# efi-shield-rev01.net
KiCad netlist of a schematic drawn in EAGLE
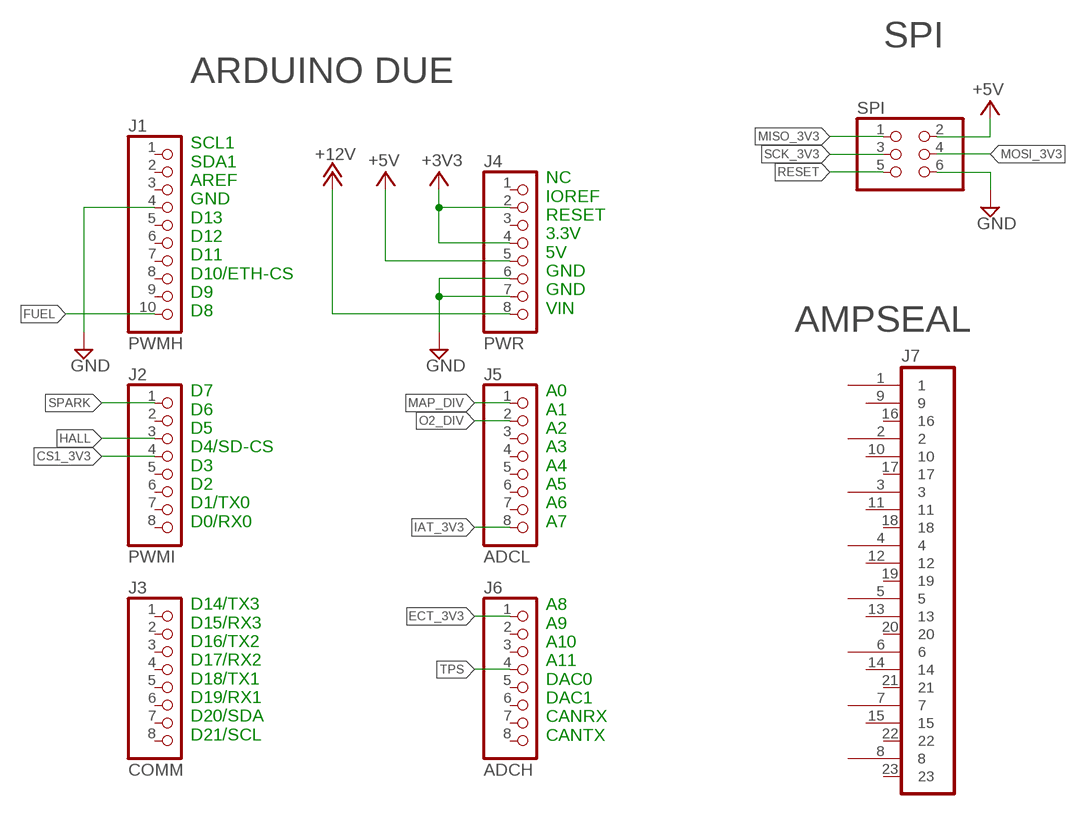
[diagram p0: schematic, sheet 1]

(export (version "E")
  (design (tool "Eeschema 10.0.6"))
  (components
    (comp (ref "J1")
      (value "PWMH")
      (footprint "eagle-import:1X10")
      (fields (field (name "MANUFACTURER") "Joe Knows Electronics"))
      (libsource (lib "eagle-import") (part "PINHD-1X10"))
    )
    (comp (ref "J2")
      (value "PWMI")
      (footprint "eagle-import:1X08")
      (fields (field (name "MANUFACTURER") "Joe Knows Electronics"))
      (libsource (lib "eagle-import") (part "PINHD-1X8"))
    )
    (comp (ref "J3")
      (value "COMM")
      (footprint "eagle-import:1X08")
      (fields (field (name "MANUFACTURER") "Joe Knows Electronics"))
      (libsource (lib "eagle-import") (part "PINHD-1X8"))
    )
    (comp (ref "J4")
      (value "PWR")
      (footprint "eagle-import:1X08")
      (fields (field (name "MANUFACTURER") "Joe Knows Electronics"))
      (libsource (lib "eagle-import") (part "PINHD-1X8"))
    )
    (comp (ref "J5")
      (value "ADCL")
      (footprint "eagle-import:1X08")
      (fields (field (name "MANUFACTURER") "Joe Knows Electronics"))
      (libsource (lib "eagle-import") (part "PINHD-1X8"))
    )
    (comp (ref "J6")
      (value "ADCH")
      (footprint "eagle-import:1X08")
      (fields (field (name "MANUFACTURER") "Joe Knows Electronics"))
      (libsource (lib "eagle-import") (part "PINHD-1X8"))
    )
    (comp (ref "J7")
      (value "AMPSEAL-23POS-HEADER")
      (footprint "eagle-import:AMPSEAL-HEADER-23POS-RA")
      (fields (field (name "MANUFACTURER") "TE Connectivity"))
      (libsource (lib "eagle-import") (part "AMPSEAL-23POS-HEADER"))
    )
    (comp (ref "SPI")
      (value "PINHD-2X3")
      (footprint "eagle-import:2X03")
      (libsource (lib "eagle-import") (part "PINHD-2X3"))
    )
  )
  (nets
    (net (code "1") (name "+3V3") (class "Default")
      (node (ref "J4") (pin "2") (pinfunction "2_2") (pintype "passive"))
      (node (ref "J4") (pin "4") (pinfunction "4_4") (pintype "passive"))
    )
    (net (code "2") (name "+5V") (class "Default")
      (node (ref "J4") (pin "5") (pinfunction "5_5") (pintype "passive"))
      (node (ref "SPI") (pin "2") (pinfunction "2_2") (pintype "passive"))
    )
    (net (code "3") (name "+12V") (class "Default")
      (node (ref "J4") (pin "8") (pinfunction "8_8") (pintype "passive"))
    )
    (net (code "4") (name "CS1_3V3") (class "Default")
      (node (ref "J2") (pin "4") (pinfunction "4_4") (pintype "passive"))
    )
    (net (code "5") (name "ECT_3V3") (class "Default")
      (node (ref "J6") (pin "1") (pinfunction "1_1") (pintype "passive"))
    )
    (net (code "6") (name "FUEL") (class "Default")
      (node (ref "J1") (pin "10") (pinfunction "10_10") (pintype "passive"))
    )
    (net (code "7") (name "GND") (class "Default")
      (node (ref "J1") (pin "4") (pinfunction "4_4") (pintype "passive"))
      (node (ref "J4") (pin "6") (pinfunction "6_6") (pintype "passive"))
      (node (ref "J4") (pin "7") (pinfunction "7_7") (pintype "passive"))
      (node (ref "SPI") (pin "6") (pinfunction "6_6") (pintype "passive"))
    )
    (net (code "8") (name "HALL") (class "Default")
      (node (ref "J2") (pin "3") (pinfunction "3_3") (pintype "passive"))
    )
    (net (code "9") (name "IAT_3V3") (class "Default")
      (node (ref "J5") (pin "8") (pinfunction "8_8") (pintype "passive"))
    )
    (net (code "10") (name "MAP_DIV") (class "Default")
      (node (ref "J5") (pin "1") (pinfunction "1_1") (pintype "passive"))
    )
    (net (code "11") (name "MISO_3V3") (class "Default")
      (node (ref "SPI") (pin "1") (pinfunction "1_1") (pintype "passive"))
    )
    (net (code "12") (name "MOSI_3V3") (class "Default")
      (node (ref "SPI") (pin "4") (pinfunction "4_4") (pintype "passive"))
    )
    (net (code "13") (name "O2_DIV") (class "Default")
      (node (ref "J5") (pin "2") (pinfunction "2_2") (pintype "passive"))
    )
    (net (code "14") (name "RESET") (class "Default")
      (node (ref "SPI") (pin "5") (pinfunction "5_5") (pintype "passive"))
    )
    (net (code "15") (name "SCK_3V3") (class "Default")
      (node (ref "SPI") (pin "3") (pinfunction "3_3") (pintype "passive"))
    )
    (net (code "16") (name "SPARK") (class "Default")
      (node (ref "J2") (pin "1") (pinfunction "1_1") (pintype "passive"))
    )
    (net (code "17") (name "TPS") (class "Default")
      (node (ref "J6") (pin "4") (pinfunction "4_4") (pintype "passive"))
    )
    (net (code "18") (name "unconnected-(J1-Pad1)") (class "Default")
      (node (ref "J1") (pin "1") (pinfunction "1_1") (pintype "passive"))
    )
    (net (code "19") (name "unconnected-(J1-Pad2)") (class "Default")
      (node (ref "J1") (pin "2") (pinfunction "2_2") (pintype "passive"))
    )
    (net (code "20") (name "unconnected-(J1-Pad3)") (class "Default")
      (node (ref "J1") (pin "3") (pinfunction "3_3") (pintype "passive"))
    )
    (net (code "21") (name "unconnected-(J1-Pad5)") (class "Default")
      (node (ref "J1") (pin "5") (pinfunction "5_5") (pintype "passive"))
    )
    (net (code "22") (name "unconnected-(J1-Pad6)") (class "Default")
      (node (ref "J1") (pin "6") (pinfunction "6_6") (pintype "passive"))
    )
    (net (code "23") (name "unconnected-(J1-Pad7)") (class "Default")
      (node (ref "J1") (pin "7") (pinfunction "7_7") (pintype "passive"))
    )
    (net (code "24") (name "unconnected-(J1-Pad8)") (class "Default")
      (node (ref "J1") (pin "8") (pinfunction "8_8") (pintype "passive"))
    )
    (net (code "25") (name "unconnected-(J1-Pad9)") (class "Default")
      (node (ref "J1") (pin "9") (pinfunction "9_9") (pintype "passive"))
    )
    (net (code "26") (name "unconnected-(J2-Pad2)") (class "Default")
      (node (ref "J2") (pin "2") (pinfunction "2_2") (pintype "passive"))
    )
    (net (code "27") (name "unconnected-(J2-Pad5)") (class "Default")
      (node (ref "J2") (pin "5") (pinfunction "5_5") (pintype "passive"))
    )
    (net (code "28") (name "unconnected-(J2-Pad6)") (class "Default")
      (node (ref "J2") (pin "6") (pinfunction "6_6") (pintype "passive"))
    )
    (net (code "29") (name "unconnected-(J2-Pad7)") (class "Default")
      (node (ref "J2") (pin "7") (pinfunction "7_7") (pintype "passive"))
    )
    (net (code "30") (name "unconnected-(J2-Pad8)") (class "Default")
      (node (ref "J2") (pin "8") (pinfunction "8_8") (pintype "passive"))
    )
    (net (code "31") (name "unconnected-(J3-Pad1)") (class "Default")
      (node (ref "J3") (pin "1") (pinfunction "1_1") (pintype "passive"))
    )
    (net (code "32") (name "unconnected-(J3-Pad2)") (class "Default")
      (node (ref "J3") (pin "2") (pinfunction "2_2") (pintype "passive"))
    )
    (net (code "33") (name "unconnected-(J3-Pad3)") (class "Default")
      (node (ref "J3") (pin "3") (pinfunction "3_3") (pintype "passive"))
    )
    (net (code "34") (name "unconnected-(J3-Pad4)") (class "Default")
      (node (ref "J3") (pin "4") (pinfunction "4_4") (pintype "passive"))
    )
    (net (code "35") (name "unconnected-(J3-Pad5)") (class "Default")
      (node (ref "J3") (pin "5") (pinfunction "5_5") (pintype "passive"))
    )
    (net (code "36") (name "unconnected-(J3-Pad6)") (class "Default")
      (node (ref "J3") (pin "6") (pinfunction "6_6") (pintype "passive"))
    )
    (net (code "37") (name "unconnected-(J3-Pad7)") (class "Default")
      (node (ref "J3") (pin "7") (pinfunction "7_7") (pintype "passive"))
    )
    (net (code "38") (name "unconnected-(J3-Pad8)") (class "Default")
      (node (ref "J3") (pin "8") (pinfunction "8_8") (pintype "passive"))
    )
    (net (code "39") (name "unconnected-(J4-Pad1)") (class "Default")
      (node (ref "J4") (pin "1") (pinfunction "1_1") (pintype "passive"))
    )
    (net (code "40") (name "unconnected-(J4-Pad3)") (class "Default")
      (node (ref "J4") (pin "3") (pinfunction "3_3") (pintype "passive"))
    )
    (net (code "41") (name "unconnected-(J5-Pad3)") (class "Default")
      (node (ref "J5") (pin "3") (pinfunction "3_3") (pintype "passive"))
    )
    (net (code "42") (name "unconnected-(J5-Pad4)") (class "Default")
      (node (ref "J5") (pin "4") (pinfunction "4_4") (pintype "passive"))
    )
    (net (code "43") (name "unconnected-(J5-Pad5)") (class "Default")
      (node (ref "J5") (pin "5") (pinfunction "5_5") (pintype "passive"))
    )
    (net (code "44") (name "unconnected-(J5-Pad6)") (class "Default")
      (node (ref "J5") (pin "6") (pinfunction "6_6") (pintype "passive"))
    )
    (net (code "45") (name "unconnected-(J5-Pad7)") (class "Default")
      (node (ref "J5") (pin "7") (pinfunction "7_7") (pintype "passive"))
    )
    (net (code "46") (name "unconnected-(J6-Pad2)") (class "Default")
      (node (ref "J6") (pin "2") (pinfunction "2_2") (pintype "passive"))
    )
    (net (code "47") (name "unconnected-(J6-Pad3)") (class "Default")
      (node (ref "J6") (pin "3") (pinfunction "3_3") (pintype "passive"))
    )
    (net (code "48") (name "unconnected-(J6-Pad5)") (class "Default")
      (node (ref "J6") (pin "5") (pinfunction "5_5") (pintype "passive"))
    )
    (net (code "49") (name "unconnected-(J6-Pad6)") (class "Default")
      (node (ref "J6") (pin "6") (pinfunction "6_6") (pintype "passive"))
    )
    (net (code "50") (name "unconnected-(J6-Pad7)") (class "Default")
      (node (ref "J6") (pin "7") (pinfunction "7_7") (pintype "passive"))
    )
    (net (code "51") (name "unconnected-(J6-Pad8)") (class "Default")
      (node (ref "J6") (pin "8") (pinfunction "8_8") (pintype "passive"))
    )
    (net (code "52") (name "unconnected-(J7-Pad1)") (class "Default")
      (node (ref "J7") (pin "1") (pinfunction "1_1") (pintype "bidirectional"))
    )
    (net (code "53") (name "unconnected-(J7-Pad2)") (class "Default")
      (node (ref "J7") (pin "2") (pinfunction "2_2") (pintype "bidirectional"))
    )
    (net (code "54") (name "unconnected-(J7-Pad3)") (class "Default")
      (node (ref "J7") (pin "3") (pinfunction "3_3") (pintype "bidirectional"))
    )
    (net (code "55") (name "unconnected-(J7-Pad4)") (class "Default")
      (node (ref "J7") (pin "4") (pinfunction "4_4") (pintype "bidirectional"))
    )
    (net (code "56") (name "unconnected-(J7-Pad5)") (class "Default")
      (node (ref "J7") (pin "5") (pinfunction "5_5") (pintype "bidirectional"))
    )
    (net (code "57") (name "unconnected-(J7-Pad6)") (class "Default")
      (node (ref "J7") (pin "6") (pinfunction "6_6") (pintype "bidirectional"))
    )
    (net (code "58") (name "unconnected-(J7-Pad7)") (class "Default")
      (node (ref "J7") (pin "7") (pinfunction "7_7") (pintype "bidirectional"))
    )
    (net (code "59") (name "unconnected-(J7-Pad8)") (class "Default")
      (node (ref "J7") (pin "8") (pinfunction "8_8") (pintype "bidirectional"))
    )
    (net (code "60") (name "unconnected-(J7-Pad9)") (class "Default")
      (node (ref "J7") (pin "9") (pinfunction "9_9") (pintype "bidirectional"))
    )
    (net (code "61") (name "unconnected-(J7-Pad10)") (class "Default")
      (node (ref "J7") (pin "10") (pinfunction "10_10") (pintype "bidirectional"))
    )
    (net (code "62") (name "unconnected-(J7-Pad11)") (class "Default")
      (node (ref "J7") (pin "11") (pinfunction "11_11") (pintype "bidirectional"))
    )
    (net (code "63") (name "unconnected-(J7-Pad12)") (class "Default")
      (node (ref "J7") (pin "12") (pinfunction "12_12") (pintype "bidirectional"))
    )
    (net (code "64") (name "unconnected-(J7-Pad13)") (class "Default")
      (node (ref "J7") (pin "13") (pinfunction "13_13") (pintype "bidirectional"))
    )
    (net (code "65") (name "unconnected-(J7-Pad14)") (class "Default")
      (node (ref "J7") (pin "14") (pinfunction "14_14") (pintype "bidirectional"))
    )
    (net (code "66") (name "unconnected-(J7-Pad15)") (class "Default")
      (node (ref "J7") (pin "15") (pinfunction "15_15") (pintype "bidirectional"))
    )
    (net (code "67") (name "unconnected-(J7-Pad16)") (class "Default")
      (node (ref "J7") (pin "16") (pinfunction "16_16") (pintype "bidirectional"))
    )
    (net (code "68") (name "unconnected-(J7-Pad17)") (class "Default")
      (node (ref "J7") (pin "17") (pinfunction "17_17") (pintype "bidirectional"))
    )
    (net (code "69") (name "unconnected-(J7-Pad18)") (class "Default")
      (node (ref "J7") (pin "18") (pinfunction "18_18") (pintype "bidirectional"))
    )
    (net (code "70") (name "unconnected-(J7-Pad19)") (class "Default")
      (node (ref "J7") (pin "19") (pinfunction "19_19") (pintype "bidirectional"))
    )
    (net (code "71") (name "unconnected-(J7-Pad20)") (class "Default")
      (node (ref "J7") (pin "20") (pinfunction "20_20") (pintype "bidirectional"))
    )
    (net (code "72") (name "unconnected-(J7-Pad21)") (class "Default")
      (node (ref "J7") (pin "21") (pinfunction "21_21") (pintype "bidirectional"))
    )
    (net (code "73") (name "unconnected-(J7-Pad22)") (class "Default")
      (node (ref "J7") (pin "22") (pinfunction "22_22") (pintype "bidirectional"))
    )
    (net (code "74") (name "unconnected-(J7-Pad23)") (class "Default")
      (node (ref "J7") (pin "23") (pinfunction "23_23") (pintype "bidirectional"))
    )
  )
)
